# schematic.net
KiCad netlist of a schematic drawn in EAGLE
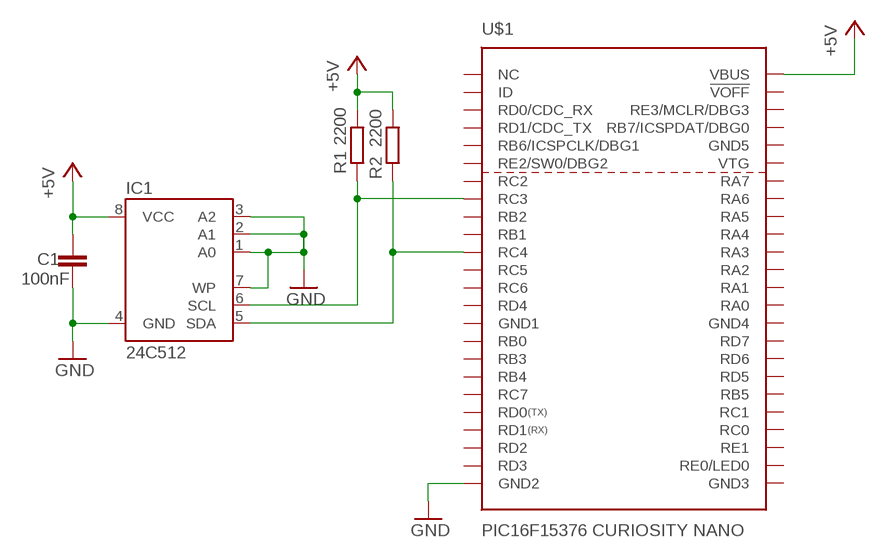
[diagram p0: schematic, sheet 1]

(export (version "E")
  (design (tool "Eeschema 10.0.6"))
  (components
    (comp (ref "C1")
      (value "100nF")
      (footprint "eagle-import:C025-024X044")
      (libsource (lib "eagle-import") (part "C-EU025-024X044"))
    )
    (comp (ref "IC1")
      (value "24C512")
      (footprint "eagle-import:DIL08")
      (fields (field (name "MPN") "AT24C1024BW-SH-B"))
      (libsource (lib "eagle-import") (part "AT24CP"))
    )
    (comp (ref "R1")
      (value "2200")
      (footprint "eagle-import:0204_7")
      (libsource (lib "eagle-import") (part "R-EU_0204/7"))
    )
    (comp (ref "R2")
      (value "2200")
      (footprint "eagle-import:0204_7")
      (libsource (lib "eagle-import") (part "R-EU_0204/7"))
    )
    (comp (ref "U$1")
      (value "PIC16F15376_CURIOSITY_NANO")
      (footprint "eagle-import:48PIN_CURIOSITY_NANO")
      (libsource (lib "eagle-import") (part "PIC16F15376_CURIOSITY_NANO"))
    )
  )
  (nets
    (net (code "1") (name "+5V") (class "Default")
      (node (ref "C1") (pin "1") (pinfunction "1_1") (pintype "passive"))
      (node (ref "IC1") (pin "8") (pinfunction "VCC_8") (pintype "power_in"))
      (node (ref "R1") (pin "2") (pinfunction "2_2") (pintype "passive"))
      (node (ref "R2") (pin "2") (pinfunction "2_2") (pintype "passive"))
      (node (ref "U$1") (pin "P$48") (pinfunction "VBUS_P$48") (pintype "power_in"))
    )
    (net (code "2") (name "/GND1") (class "Default")
      (node (ref "U$1") (pin "P$15") (pinfunction "GND1_P$15") (pintype "power_in"))
    )
    (net (code "3") (name "/GND3") (class "Default")
      (node (ref "U$1") (pin "P$25") (pinfunction "GND3_P$25") (pintype "power_in"))
    )
    (net (code "4") (name "/GND4") (class "Default")
      (node (ref "U$1") (pin "P$34") (pinfunction "GND4_P$34") (pintype "power_in"))
    )
    (net (code "5") (name "/GND5") (class "Default")
      (node (ref "U$1") (pin "P$44") (pinfunction "GND5_P$44") (pintype "power_in"))
    )
    (net (code "6") (name "/VTG") (class "Default")
      (node (ref "U$1") (pin "P$43") (pinfunction "VTG_P$43") (pintype "power_in"))
    )
    (net (code "7") (name "/~{VOFF}") (class "Default")
      (node (ref "U$1") (pin "P$47") (pinfunction "~{VOFF}_P$47") (pintype "power_in"))
    )
    (net (code "8") (name "GND") (class "Default")
      (node (ref "C1") (pin "2") (pinfunction "2_2") (pintype "passive"))
      (node (ref "IC1") (pin "1") (pinfunction "A0_1") (pintype "input"))
      (node (ref "IC1") (pin "2") (pinfunction "A1_2") (pintype "input"))
      (node (ref "IC1") (pin "3") (pinfunction "A2_3") (pintype "input"))
      (node (ref "IC1") (pin "4") (pinfunction "GND_4") (pintype "power_in"))
      (node (ref "IC1") (pin "7") (pinfunction "WP_7") (pintype "input"))
      (node (ref "U$1") (pin "P$24") (pinfunction "GND2_P$24") (pintype "power_in"))
    )
    (net (code "9") (name "Net-(IC1-SCL)") (class "Default")
      (node (ref "IC1") (pin "6") (pinfunction "SCL_6") (pintype "bidirectional"))
      (node (ref "R1") (pin "1") (pinfunction "1_1") (pintype "passive"))
      (node (ref "U$1") (pin "P$8") (pinfunction "RC3_P$8") (pintype "bidirectional"))
    )
    (net (code "10") (name "Net-(IC1-SDA)") (class "Default")
      (node (ref "IC1") (pin "5") (pinfunction "SDA_5") (pintype "bidirectional"))
      (node (ref "R2") (pin "1") (pinfunction "1_1") (pintype "passive"))
      (node (ref "U$1") (pin "P$11") (pinfunction "RC4_P$11") (pintype "bidirectional"))
    )
    (net (code "11") (name "unconnected-(U$1-ID-PadP$2)") (class "Default")
      (node (ref "U$1") (pin "P$2") (pinfunction "ID_P$2") (pintype "bidirectional"))
    )
    (net (code "12") (name "unconnected-(U$1-NC-PadP$1)") (class "Default")
      (node (ref "U$1") (pin "P$1") (pinfunction "NC_P$1") (pintype "no_connect"))
    )
    (net (code "13") (name "unconnected-(U$1-RA0-PadP$35)") (class "Default")
      (node (ref "U$1") (pin "P$35") (pinfunction "RA0_P$35") (pintype "bidirectional"))
    )
    (net (code "14") (name "unconnected-(U$1-RA1-PadP$36)") (class "Default")
      (node (ref "U$1") (pin "P$36") (pinfunction "RA1_P$36") (pintype "bidirectional"))
    )
    (net (code "15") (name "unconnected-(U$1-RA2-PadP$37)") (class "Default")
      (node (ref "U$1") (pin "P$37") (pinfunction "RA2_P$37") (pintype "bidirectional"))
    )
    (net (code "16") (name "unconnected-(U$1-RA3-PadP$38)") (class "Default")
      (node (ref "U$1") (pin "P$38") (pinfunction "RA3_P$38") (pintype "bidirectional"))
    )
    (net (code "17") (name "unconnected-(U$1-RA4-PadP$39)") (class "Default")
      (node (ref "U$1") (pin "P$39") (pinfunction "RA4_P$39") (pintype "bidirectional"))
    )
    (net (code "18") (name "unconnected-(U$1-RA5-PadP$40)") (class "Default")
      (node (ref "U$1") (pin "P$40") (pinfunction "RA5_P$40") (pintype "bidirectional"))
    )
    (net (code "19") (name "unconnected-(U$1-RA6-PadP$41)") (class "Default")
      (node (ref "U$1") (pin "P$41") (pinfunction "RA6_P$41") (pintype "bidirectional"))
    )
    (net (code "20") (name "unconnected-(U$1-RA7-PadP$42)") (class "Default")
      (node (ref "U$1") (pin "P$42") (pinfunction "RA7_P$42") (pintype "bidirectional"))
    )
    (net (code "21") (name "unconnected-(U$1-RB0-PadP$16)") (class "Default")
      (node (ref "U$1") (pin "P$16") (pinfunction "RB0_P$16") (pintype "bidirectional"))
    )
    (net (code "22") (name "unconnected-(U$1-RB1-PadP$10)") (class "Default")
      (node (ref "U$1") (pin "P$10") (pinfunction "RB1_P$10") (pintype "bidirectional"))
    )
    (net (code "23") (name "unconnected-(U$1-RB2-PadP$9)") (class "Default")
      (node (ref "U$1") (pin "P$9") (pinfunction "RB2_P$9") (pintype "bidirectional"))
    )
    (net (code "24") (name "unconnected-(U$1-RB3-PadP$17)") (class "Default")
      (node (ref "U$1") (pin "P$17") (pinfunction "RB3_P$17") (pintype "bidirectional"))
    )
    (net (code "25") (name "unconnected-(U$1-RB4-PadP$18)") (class "Default")
      (node (ref "U$1") (pin "P$18") (pinfunction "RB4_P$18") (pintype "bidirectional"))
    )
    (net (code "26") (name "unconnected-(U$1-RB5-PadP$30)") (class "Default")
      (node (ref "U$1") (pin "P$30") (pinfunction "RB5_P$30") (pintype "bidirectional"))
    )
    (net (code "27") (name "unconnected-(U$1-RB6{slash}ICSPCLK{slash}DBG1-PadP$5)") (class "Default")
      (node (ref "U$1") (pin "P$5") (pinfunction "RB6/ICSPCLK/DBG1_P$5") (pintype "bidirectional"))
    )
    (net (code "28") (name "unconnected-(U$1-RB7{slash}ICSPDAT{slash}DBG0-PadP$45)") (class "Default")
      (node (ref "U$1") (pin "P$45") (pinfunction "RB7/ICSPDAT/DBG0_P$45") (pintype "bidirectional"))
    )
    (net (code "29") (name "unconnected-(U$1-RC0-PadP$28)") (class "Default")
      (node (ref "U$1") (pin "P$28") (pinfunction "RC0_P$28") (pintype "bidirectional"))
    )
    (net (code "30") (name "unconnected-(U$1-RC1-PadP$29)") (class "Default")
      (node (ref "U$1") (pin "P$29") (pinfunction "RC1_P$29") (pintype "bidirectional"))
    )
    (net (code "31") (name "unconnected-(U$1-RC2-PadP$7)") (class "Default")
      (node (ref "U$1") (pin "P$7") (pinfunction "RC2_P$7") (pintype "bidirectional"))
    )
    (net (code "32") (name "unconnected-(U$1-RC5-PadP$12)") (class "Default")
      (node (ref "U$1") (pin "P$12") (pinfunction "RC5_P$12") (pintype "bidirectional"))
    )
    (net (code "33") (name "unconnected-(U$1-RC6-PadP$13)") (class "Default")
      (node (ref "U$1") (pin "P$13") (pinfunction "RC6_P$13") (pintype "bidirectional"))
    )
    (net (code "34") (name "unconnected-(U$1-RC7-PadP$19)") (class "Default")
      (node (ref "U$1") (pin "P$19") (pinfunction "RC7_P$19") (pintype "bidirectional"))
    )
    (net (code "35") (name "unconnected-(U$1-RD0-PadP$20)") (class "Default")
      (node (ref "U$1") (pin "P$20") (pinfunction "RD0_P$20") (pintype "bidirectional"))
    )
    (net (code "36") (name "unconnected-(U$1-RD0{slash}CDC_RX-PadP$3)") (class "Default")
      (node (ref "U$1") (pin "P$3") (pinfunction "RD0/CDC_RX_P$3") (pintype "bidirectional"))
    )
    (net (code "37") (name "unconnected-(U$1-RD1-PadP$21)") (class "Default")
      (node (ref "U$1") (pin "P$21") (pinfunction "RD1_P$21") (pintype "bidirectional"))
    )
    (net (code "38") (name "unconnected-(U$1-RD1{slash}CDC_TX-PadP$4)") (class "Default")
      (node (ref "U$1") (pin "P$4") (pinfunction "RD1/CDC_TX_P$4") (pintype "bidirectional"))
    )
    (net (code "39") (name "unconnected-(U$1-RD2-PadP$22)") (class "Default")
      (node (ref "U$1") (pin "P$22") (pinfunction "RD2_P$22") (pintype "bidirectional"))
    )
    (net (code "40") (name "unconnected-(U$1-RD3-PadP$23)") (class "Default")
      (node (ref "U$1") (pin "P$23") (pinfunction "RD3_P$23") (pintype "bidirectional"))
    )
    (net (code "41") (name "unconnected-(U$1-RD4-PadP$14)") (class "Default")
      (node (ref "U$1") (pin "P$14") (pinfunction "RD4_P$14") (pintype "bidirectional"))
    )
    (net (code "42") (name "unconnected-(U$1-RD5-PadP$31)") (class "Default")
      (node (ref "U$1") (pin "P$31") (pinfunction "RD5_P$31") (pintype "bidirectional"))
    )
    (net (code "43") (name "unconnected-(U$1-RD6-PadP$32)") (class "Default")
      (node (ref "U$1") (pin "P$32") (pinfunction "RD6_P$32") (pintype "bidirectional"))
    )
    (net (code "44") (name "unconnected-(U$1-RD7-PadP$33)") (class "Default")
      (node (ref "U$1") (pin "P$33") (pinfunction "RD7_P$33") (pintype "bidirectional"))
    )
    (net (code "45") (name "unconnected-(U$1-RE0{slash}LED0-PadP$26)") (class "Default")
      (node (ref "U$1") (pin "P$26") (pinfunction "RE0/LED0_P$26") (pintype "bidirectional"))
    )
    (net (code "46") (name "unconnected-(U$1-RE1-PadP$27)") (class "Default")
      (node (ref "U$1") (pin "P$27") (pinfunction "RE1_P$27") (pintype "bidirectional"))
    )
    (net (code "47") (name "unconnected-(U$1-RE2{slash}SW0{slash}DBG2-PadP$6)") (class "Default")
      (node (ref "U$1") (pin "P$6") (pinfunction "RE2/SW0/DBG2_P$6") (pintype "bidirectional"))
    )
    (net (code "48") (name "unconnected-(U$1-RE3{slash}MCLR{slash}DBG3-PadP$46)") (class "Default")
      (node (ref "U$1") (pin "P$46") (pinfunction "RE3/MCLR/DBG3_P$46") (pintype "bidirectional"))
    )
  )
)
